# VDMEDA_IOExpander.net
KiCad netlist of a schematic drawn in Altium Designer
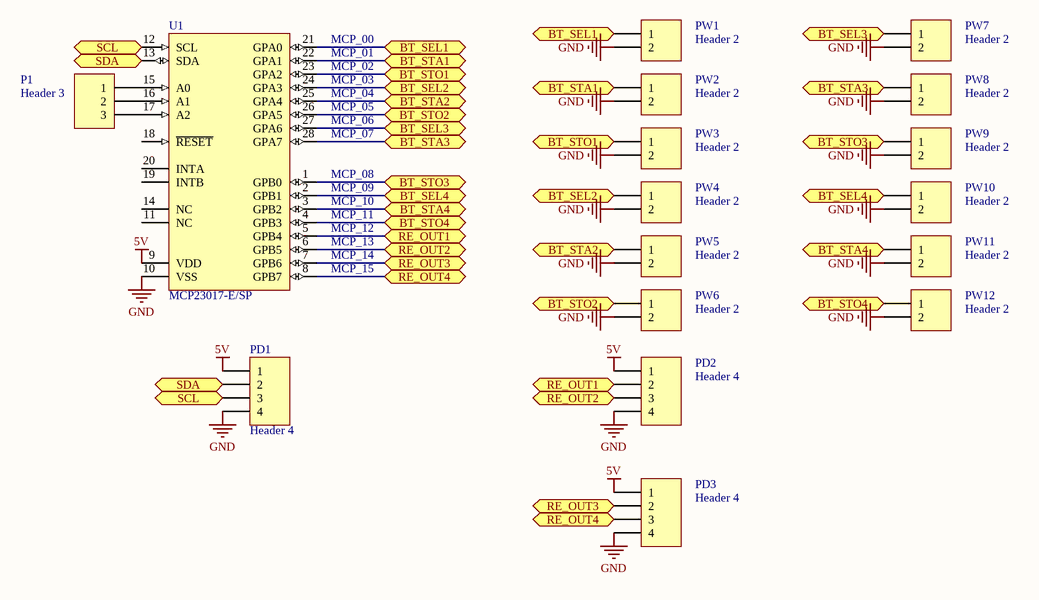
[diagram p0: VDMEDA_IOExpander.SchDoc]

(export (version "E")
  (design (tool "Eeschema 10.0.6"))
  (components
    (comp (ref "P1")
      (value "Header 3")
      (footprint "HDR1X3")
      (description "Header, 3-Pin")
      (fields (field (name "PUBLISHER") "Altium Limited"))
      (libsource (lib "Miscellaneous Connectors") (part "Header 3"))
    )
    (comp (ref "PD1")
      (value "Header 4")
      (footprint "HDR1X4")
      (description "Header, 4-Pin")
      (fields (field (name "PUBLISHER") "Altium Limited"))
      (libsource (lib "Miscellaneous Connectors") (part "Header 4"))
    )
    (comp (ref "PD2")
      (value "Header 4")
      (footprint "HDR1X4")
      (description "Header, 4-Pin")
      (fields (field (name "PUBLISHER") "Altium Limited"))
      (libsource (lib "Miscellaneous Connectors") (part "Header 4"))
    )
    (comp (ref "PD3")
      (value "Header 4")
      (footprint "HDR1X4")
      (description "Header, 4-Pin")
      (fields (field (name "PUBLISHER") "Altium Limited"))
      (libsource (lib "Miscellaneous Connectors") (part "Header 4"))
    )
    (comp (ref "PW1")
      (value "Header 2")
      (footprint "TO-220_A")
      (description "Header, 2-Pin")
      (fields (field (name "PUBLISHER") "Altium Limited"))
      (libsource (lib "Miscellaneous Connectors") (part "Header 2"))
    )
    (comp (ref "PW2")
      (value "Header 2")
      (footprint "TO-220_A")
      (description "Header, 2-Pin")
      (fields (field (name "PUBLISHER") "Altium Limited"))
      (libsource (lib "Miscellaneous Connectors") (part "Header 2"))
    )
    (comp (ref "PW3")
      (value "Header 2")
      (footprint "TO-220_A")
      (description "Header, 2-Pin")
      (fields (field (name "PUBLISHER") "Altium Limited"))
      (libsource (lib "Miscellaneous Connectors") (part "Header 2"))
    )
    (comp (ref "PW4")
      (value "Header 2")
      (footprint "TO-220_A")
      (description "Header, 2-Pin")
      (fields (field (name "PUBLISHER") "Altium Limited"))
      (libsource (lib "Miscellaneous Connectors") (part "Header 2"))
    )
    (comp (ref "PW5")
      (value "Header 2")
      (footprint "TO-220_A")
      (description "Header, 2-Pin")
      (fields (field (name "PUBLISHER") "Altium Limited"))
      (libsource (lib "Miscellaneous Connectors") (part "Header 2"))
    )
    (comp (ref "PW6")
      (value "Header 2")
      (footprint "TO-220_A")
      (description "Header, 2-Pin")
      (fields (field (name "PUBLISHER") "Altium Limited"))
      (libsource (lib "Miscellaneous Connectors") (part "Header 2"))
    )
    (comp (ref "PW7")
      (value "Header 2")
      (footprint "TO-220_A")
      (description "Header, 2-Pin")
      (fields (field (name "PUBLISHER") "Altium Limited"))
      (libsource (lib "Miscellaneous Connectors") (part "Header 2"))
    )
    (comp (ref "PW8")
      (value "Header 2")
      (footprint "TO-220_A")
      (description "Header, 2-Pin")
      (fields (field (name "PUBLISHER") "Altium Limited"))
      (libsource (lib "Miscellaneous Connectors") (part "Header 2"))
    )
    (comp (ref "PW9")
      (value "Header 2")
      (footprint "TO-220_A")
      (description "Header, 2-Pin")
      (fields (field (name "PUBLISHER") "Altium Limited"))
      (libsource (lib "Miscellaneous Connectors") (part "Header 2"))
    )
    (comp (ref "PW10")
      (value "Header 2")
      (footprint "TO-220_A")
      (description "Header, 2-Pin")
      (fields (field (name "PUBLISHER") "Altium Limited"))
      (libsource (lib "Miscellaneous Connectors") (part "Header 2"))
    )
    (comp (ref "PW11")
      (value "Header 2")
      (footprint "TO-220_A")
      (description "Header, 2-Pin")
      (fields (field (name "PUBLISHER") "Altium Limited"))
      (libsource (lib "Miscellaneous Connectors") (part "Header 2"))
    )
    (comp (ref "PW12")
      (value "Header 2")
      (footprint "TO-220_A")
      (description "Header, 2-Pin")
      (fields (field (name "PUBLISHER") "Altium Limited"))
      (libsource (lib "Miscellaneous Connectors") (part "Header 2"))
    )
    (comp (ref "U1")
      (value "MCP23017-E/SP")
      (footprint "SPDIP300-SP28")
      (description "16-Bit I/O Expander with Serial Interface, 28-Pin SPDIP, Extended Temperature")
      (fields (field (name "PUBLISHER") "Altium Limited"))
      (libsource (lib "Microchip Interface") (part "MCP23017-E/SP"))
    )
  )
  (nets
    (net (code "1") (name "/BT_SEL1") (class "Default")
      (node (ref "PW1") (pin "1") (pinfunction "1_1") (pintype "passive"))
      (node (ref "U1") (pin "21") (pinfunction "GPA0_21") (pintype "bidirectional"))
    )
    (net (code "2") (name "/BT_SEL2") (class "Default")
      (node (ref "PW4") (pin "1") (pinfunction "1_1") (pintype "passive"))
      (node (ref "U1") (pin "24") (pinfunction "GPA3_24") (pintype "bidirectional"))
    )
    (net (code "3") (name "/BT_SEL3") (class "Default")
      (node (ref "PW7") (pin "1") (pinfunction "1_1") (pintype "passive"))
      (node (ref "U1") (pin "27") (pinfunction "GPA6_27") (pintype "bidirectional"))
    )
    (net (code "4") (name "/BT_SEL4") (class "Default")
      (node (ref "PW10") (pin "1") (pinfunction "1_1") (pintype "passive"))
      (node (ref "U1") (pin "2") (pinfunction "GPB1_2") (pintype "bidirectional"))
    )
    (net (code "5") (name "/BT_STA1") (class "Default")
      (node (ref "PW2") (pin "1") (pinfunction "1_1") (pintype "passive"))
      (node (ref "U1") (pin "22") (pinfunction "GPA1_22") (pintype "bidirectional"))
    )
    (net (code "6") (name "/BT_STA2") (class "Default")
      (node (ref "PW5") (pin "1") (pinfunction "1_1") (pintype "passive"))
      (node (ref "U1") (pin "25") (pinfunction "GPA4_25") (pintype "bidirectional"))
    )
    (net (code "7") (name "/BT_STA3") (class "Default")
      (node (ref "PW8") (pin "1") (pinfunction "1_1") (pintype "passive"))
      (node (ref "U1") (pin "28") (pinfunction "GPA7_28") (pintype "bidirectional"))
    )
    (net (code "8") (name "/BT_STA4") (class "Default")
      (node (ref "PW11") (pin "1") (pinfunction "1_1") (pintype "passive"))
      (node (ref "U1") (pin "3") (pinfunction "GPB2_3") (pintype "bidirectional"))
    )
    (net (code "9") (name "/BT_STO1") (class "Default")
      (node (ref "PW3") (pin "1") (pinfunction "1_1") (pintype "passive"))
      (node (ref "U1") (pin "23") (pinfunction "GPA2_23") (pintype "bidirectional"))
    )
    (net (code "10") (name "/BT_STO2") (class "Default")
      (node (ref "PW6") (pin "1") (pinfunction "1_1") (pintype "passive"))
      (node (ref "U1") (pin "26") (pinfunction "GPA5_26") (pintype "bidirectional"))
    )
    (net (code "11") (name "/BT_STO3") (class "Default")
      (node (ref "PW9") (pin "1") (pinfunction "1_1") (pintype "passive"))
      (node (ref "U1") (pin "1") (pinfunction "GPB0_1") (pintype "bidirectional"))
    )
    (net (code "12") (name "/BT_STO4") (class "Default")
      (node (ref "PW12") (pin "1") (pinfunction "1_1") (pintype "passive"))
      (node (ref "U1") (pin "4") (pinfunction "GPB3_4") (pintype "bidirectional"))
    )
    (net (code "13") (name "/RE_OUT1") (class "Default")
      (node (ref "PD2") (pin "2") (pinfunction "2_2") (pintype "passive"))
      (node (ref "U1") (pin "5") (pinfunction "GPB4_5") (pintype "bidirectional"))
    )
    (net (code "14") (name "/RE_OUT2") (class "Default")
      (node (ref "PD2") (pin "3") (pinfunction "3_3") (pintype "passive"))
      (node (ref "U1") (pin "6") (pinfunction "GPB5_6") (pintype "bidirectional"))
    )
    (net (code "15") (name "/RE_OUT3") (class "Default")
      (node (ref "PD3") (pin "2") (pinfunction "2_2") (pintype "passive"))
      (node (ref "U1") (pin "7") (pinfunction "GPB6_7") (pintype "bidirectional"))
    )
    (net (code "16") (name "/RE_OUT4") (class "Default")
      (node (ref "PD3") (pin "3") (pinfunction "3_3") (pintype "passive"))
      (node (ref "U1") (pin "8") (pinfunction "GPB7_8") (pintype "bidirectional"))
    )
    (net (code "17") (name "/SCL") (class "Default")
      (node (ref "PD1") (pin "3") (pinfunction "3_3") (pintype "passive"))
      (node (ref "U1") (pin "12") (pinfunction "SCL_12") (pintype "input"))
    )
    (net (code "18") (name "/SDA") (class "Default")
      (node (ref "PD1") (pin "2") (pinfunction "2_2") (pintype "passive"))
      (node (ref "U1") (pin "13") (pinfunction "SDA_13") (pintype "bidirectional"))
    )
    (net (code "19") (name "5V") (class "Default")
      (node (ref "PD1") (pin "1") (pinfunction "1_1") (pintype "passive"))
      (node (ref "PD2") (pin "1") (pinfunction "1_1") (pintype "passive"))
      (node (ref "PD3") (pin "1") (pinfunction "1_1") (pintype "passive"))
      (node (ref "U1") (pin "9") (pinfunction "VDD_9") (pintype "power_in"))
    )
    (net (code "20") (name "GND") (class "Default")
      (node (ref "PD1") (pin "4") (pinfunction "4_4") (pintype "passive"))
      (node (ref "PD2") (pin "4") (pinfunction "4_4") (pintype "passive"))
      (node (ref "PD3") (pin "4") (pinfunction "4_4") (pintype "passive"))
      (node (ref "PW1") (pin "2") (pinfunction "2_2") (pintype "passive"))
      (node (ref "PW10") (pin "2") (pinfunction "2_2") (pintype "passive"))
      (node (ref "PW11") (pin "2") (pinfunction "2_2") (pintype "passive"))
      (node (ref "PW12") (pin "2") (pinfunction "2_2") (pintype "passive"))
      (node (ref "PW2") (pin "2") (pinfunction "2_2") (pintype "passive"))
      (node (ref "PW3") (pin "2") (pinfunction "2_2") (pintype "passive"))
      (node (ref "PW4") (pin "2") (pinfunction "2_2") (pintype "passive"))
      (node (ref "PW5") (pin "2") (pinfunction "2_2") (pintype "passive"))
      (node (ref "PW6") (pin "2") (pinfunction "2_2") (pintype "passive"))
      (node (ref "PW7") (pin "2") (pinfunction "2_2") (pintype "passive"))
      (node (ref "PW8") (pin "2") (pinfunction "2_2") (pintype "passive"))
      (node (ref "PW9") (pin "2") (pinfunction "2_2") (pintype "passive"))
      (node (ref "U1") (pin "10") (pinfunction "VSS_10") (pintype "power_in"))
    )
    (net (code "21") (name "Net-(U1-A0)") (class "Default")
      (node (ref "P1") (pin "1") (pinfunction "1_1") (pintype "passive"))
      (node (ref "U1") (pin "15") (pinfunction "A0_15") (pintype "input"))
    )
    (net (code "22") (name "Net-(U1-A1)") (class "Default")
      (node (ref "P1") (pin "2") (pinfunction "2_2") (pintype "passive"))
      (node (ref "U1") (pin "16") (pinfunction "A1_16") (pintype "input"))
    )
    (net (code "23") (name "Net-(U1-A2)") (class "Default")
      (node (ref "P1") (pin "3") (pinfunction "3_3") (pintype "passive"))
      (node (ref "U1") (pin "17") (pinfunction "A2_17") (pintype "input"))
    )
    (net (code "24") (name "unconnected-(U1-INTA-Pad20)") (class "Default")
      (node (ref "U1") (pin "20") (pinfunction "INTA_20") (pintype "open_collector"))
    )
    (net (code "25") (name "unconnected-(U1-INTB-Pad19)") (class "Default")
      (node (ref "U1") (pin "19") (pinfunction "INTB_19") (pintype "open_collector"))
    )
    (net (code "26") (name "unconnected-(U1-NC-Pad11)") (class "Default")
      (node (ref "U1") (pin "11") (pinfunction "NC_11") (pintype "passive"))
    )
    (net (code "27") (name "unconnected-(U1-NC-Pad14)") (class "Default")
      (node (ref "U1") (pin "14") (pinfunction "NC_14") (pintype "passive"))
    )
    (net (code "28") (name "unconnected-(U1-~{RESET}-Pad18)") (class "Default")
      (node (ref "U1") (pin "18") (pinfunction "~{RESET}_18") (pintype "input"))
    )
  )
)
